# Sheet1.net
KiCad netlist of a schematic drawn in Altium Designer
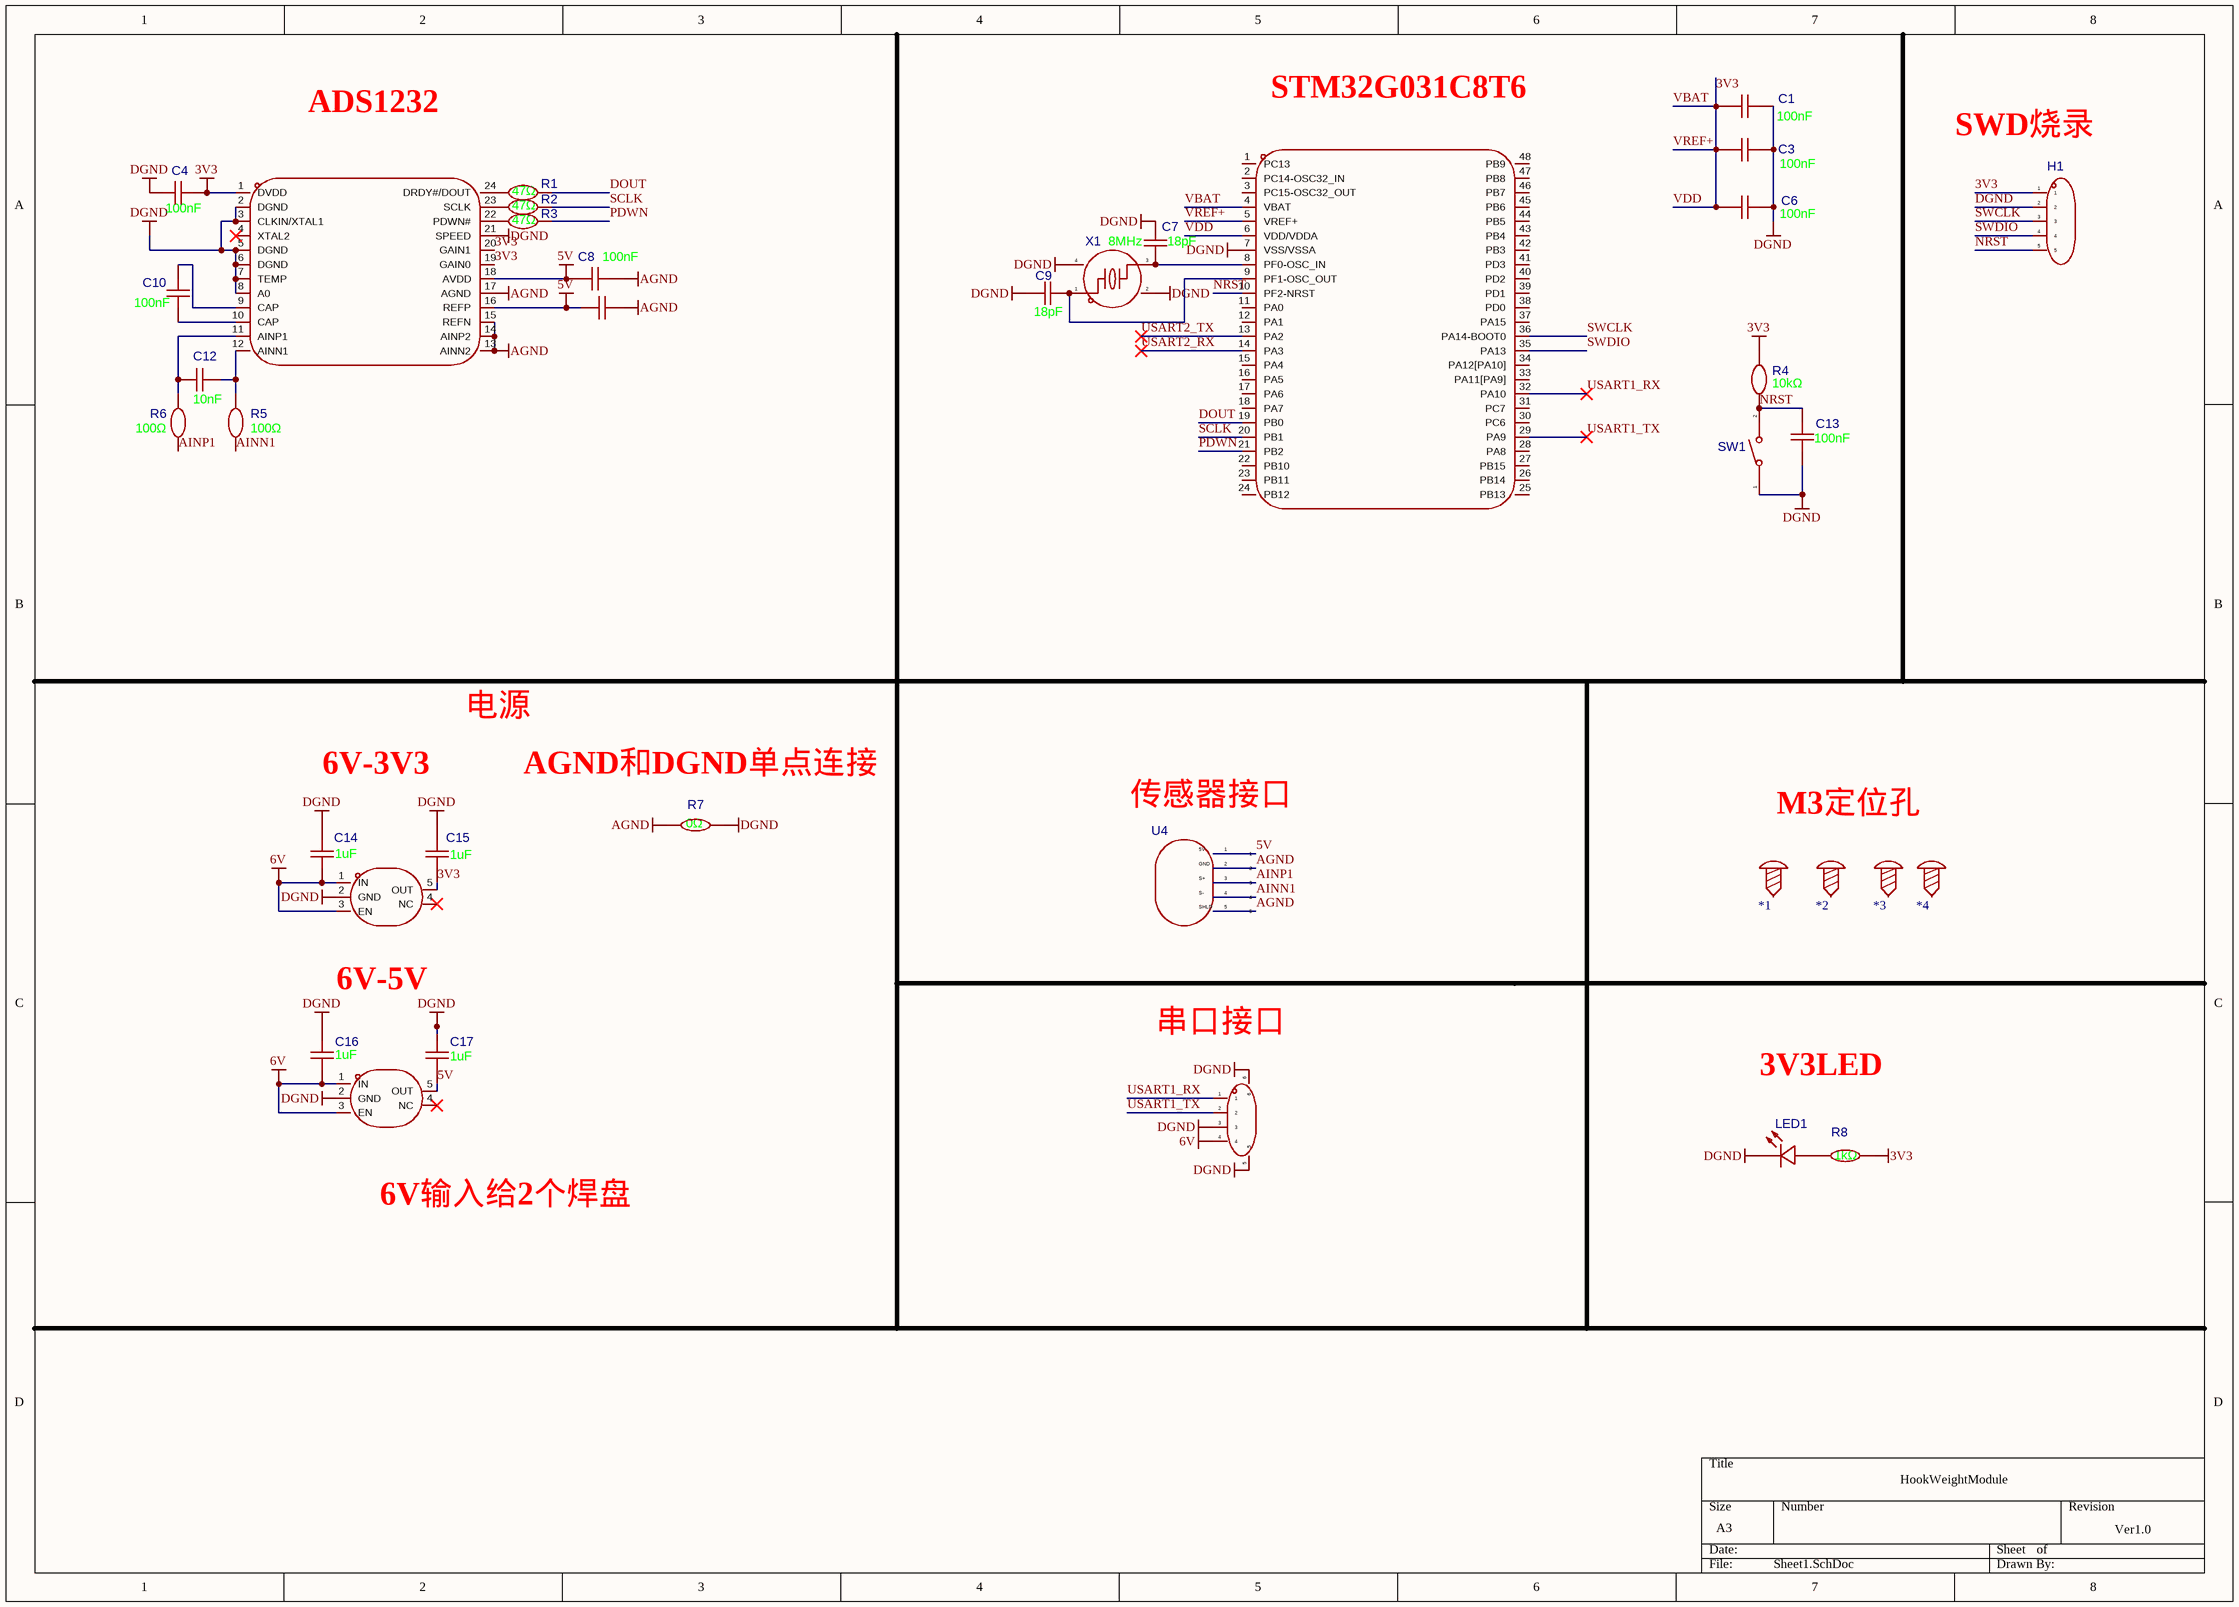
[diagram p0: Sheet1.SchDoc]

(export (version "E")
  (design (tool "Eeschema 10.0.6"))
  (components
    (comp (ref "*1") (value "螺丝孔_1") (footprint "M3螺丝") (libsource (lib "螺丝孔_1") (part "螺丝孔_1")))
    (comp (ref "*2") (value "螺丝孔_1") (footprint "M3螺丝") (libsource (lib "螺丝孔_1") (part "螺丝孔_1")))
    (comp (ref "*3") (value "螺丝孔_1") (footprint "M3螺丝") (libsource (lib "螺丝孔_1") (part "螺丝孔_1")))
    (comp (ref "*4") (value "螺丝孔_1") (footprint "M3螺丝") (libsource (lib "螺丝孔_1") (part "螺丝孔_1")))
    (comp (ref "C1")
      (value "100nF")
      (footprint "C0402")
      (description "容值:100nF;精度:±10%;额定电压:16V;温度系数:X7R;")
      (fields (field (name "MANUFACTURER") "YAGEO(国巨)") (field (name "MANUFACTURERPART") "CC0402KRX7R7BB104"))
      (libsource (lib "CC0402KRX7R7BB104") (part "cc0402krx7r7bb104"))
    )
    (comp (ref "C3")
      (value "100nF")
      (footprint "C0402")
      (description "容值:100nF;精度:±10%;额定电压:16V;温度系数:X7R;")
      (fields (field (name "MANUFACTURER") "YAGEO(国巨)") (field (name "MANUFACTURERPART") "CC0402KRX7R7BB104"))
      (libsource (lib "CC0402KRX7R7BB104") (part "cc0402krx7r7bb104"))
    )
    (comp (ref "C4")
      (value "100nF")
      (footprint "C0402")
      (description "容值:100nF;精度:±10%;额定电压:16V;温度系数:X7R;")
      (fields (field (name "MANUFACTURER") "YAGEO(国巨)") (field (name "MANUFACTURERPART") "CC0402KRX7R7BB104"))
      (libsource (lib "CC0402KRX7R7BB104") (part "cc0402krx7r7bb104"))
    )
    (comp (ref "C6")
      (value "100nF")
      (footprint "C0402")
      (description "容值:100nF;精度:±10%;额定电压:16V;温度系数:X7R;")
      (fields (field (name "MANUFACTURER") "YAGEO(国巨)") (field (name "MANUFACTURERPART") "CC0402KRX7R7BB104"))
      (libsource (lib "CC0402KRX7R7BB104") (part "cc0402krx7r7bb104"))
    )
    (comp (ref "C7")
      (value "18pF")
      (footprint "C0402")
      (description "容值:18pF;精度:±5%;额定电压:50V;温度系数:NP0;")
      (fields (field (name "MANUFACTURER") "YAGEO(国巨)") (field (name "MANUFACTURERPART") "CC0402JRNPO9BN180"))
      (libsource (lib "CC0402JRNPO9BN180") (part "cc0402jrnpo9bn180"))
    )
    (comp (ref "C8")
      (value "100nF")
      (footprint "C0402")
      (description "容值:100nF;精度:±10%;额定电压:16V;温度系数:X7R;")
      (fields (field (name "MANUFACTURER") "YAGEO(国巨)") (field (name "MANUFACTURERPART") "CC0402KRX7R7BB104"))
      (libsource (lib "CC0402KRX7R7BB104") (part "cc0402krx7r7bb104"))
    )
    (comp (ref "C9")
      (value "18pF")
      (footprint "C0402")
      (description "容值:18pF;精度:±5%;额定电压:50V;温度系数:NP0;")
      (fields (field (name "MANUFACTURER") "YAGEO(国巨)") (field (name "MANUFACTURERPART") "CC0402JRNPO9BN180"))
      (libsource (lib "CC0402JRNPO9BN180") (part "cc0402jrnpo9bn180"))
    )
    (comp (ref "C10")
      (value "100nF")
      (footprint "C0402")
      (description "容值:100nF;精度:±10%;额定电压:16V;温度系数:X7R;")
      (fields (field (name "MANUFACTURER") "YAGEO(国巨)") (field (name "MANUFACTURERPART") "CC0402KRX7R7BB104"))
      (libsource (lib "CC0402KRX7R7BB104") (part "cc0402krx7r7bb104"))
    )
    (comp (ref "C11")
      (value "cl21b103kbannnc")
      (footprint "C0805")
      (description "容值:10nF;精度:±10%;额定电压:50V;温度系数:X7R;")
      (fields (field (name "MANUFACTURER") "SAMSUNG(三星)") (field (name "MANUFACTURERPART") "CL21B103KBANNNC"))
      (libsource (lib "Schlib1") (part "cl21b103kbannnc"))
    )
    (comp (ref "C12")
      (value "10nF")
      (footprint "C0805")
      (description "容值:10nF;精度:±10%;额定电压:50V;温度系数:X7R;")
      (fields (field (name "MANUFACTURER") "SAMSUNG(三星)") (field (name "MANUFACTURERPART") "CL21B103KBANNNC"))
      (libsource (lib "Schlib1") (part "cl21b103kbannnc"))
    )
    (comp (ref "C13")
      (value "100nF")
      (footprint "C0402")
      (description "容值:100nF;精度:±10%;额定电压:16V;温度系数:X7R;")
      (fields (field (name "MANUFACTURER") "YAGEO(国巨)") (field (name "MANUFACTURERPART") "CC0402KRX7R7BB104"))
      (libsource (lib "CC0402KRX7R7BB104") (part "cc0402krx7r7bb104"))
    )
    (comp (ref "C14")
      (value "1uF")
      (footprint "C0603")
      (description "容值:1uF;精度:±10%;额定电压:50V;温度系数:X5R;")
      (fields (field (name "MANUFACTURER") "HRE(芯声)") (field (name "MANUFACTURERPART") "CGA0603X5R105K500JT"))
      (libsource (lib "CGA0603X5R105K500JT") (part "cga0603x5r105k500jt"))
    )
    (comp (ref "C15")
      (value "1uF")
      (footprint "C0603")
      (description "容值:1uF;精度:±10%;额定电压:50V;温度系数:X5R;")
      (fields (field (name "MANUFACTURER") "HRE(芯声)") (field (name "MANUFACTURERPART") "CGA0603X5R105K500JT"))
      (libsource (lib "CGA0603X5R105K500JT") (part "cga0603x5r105k500jt"))
    )
    (comp (ref "C16")
      (value "1uF")
      (footprint "C0603")
      (description "容值:1uF;精度:±10%;额定电压:50V;温度系数:X5R;")
      (fields (field (name "MANUFACTURER") "HRE(芯声)") (field (name "MANUFACTURERPART") "CGA0603X5R105K500JT"))
      (libsource (lib "CGA0603X5R105K500JT") (part "cga0603x5r105k500jt"))
    )
    (comp (ref "C17")
      (value "1uF")
      (footprint "C0603")
      (description "容值:1uF;精度:±10%;额定电压:50V;温度系数:X5R;")
      (fields (field (name "MANUFACTURER") "HRE(芯声)") (field (name "MANUFACTURERPART") "CGA0603X5R105K500JT"))
      (libsource (lib "CGA0603X5R105K500JT") (part "cga0603x5r105k500jt"))
    )
    (comp (ref "H1")
      (value "pz254v-11-05p")
      (footprint "HDR-TH_5P-P2.54-V-M")
      (fields (field (name "MANUFACTURER") "XFCN(兴飞)") (field (name "MANUFACTURERPART") "PZ254V-11-05P"))
      (libsource (lib "PZ254V-11-05P") (part "pz254v-11-05p"))
    )
    (comp (ref "LED1")
      (value "ltst-c190kskt")
      (footprint "LED0603-RD")
      (fields (field (name "MANUFACTURER") "LITEON(光宝)") (field (name "MANUFACTURERPART") "LTST-C190KSKT"))
      (libsource (lib "Schlib1") (part "ltst-c190kskt"))
    )
    (comp (ref "R1")
      (value "47Ω")
      (footprint "R0402")
      (description "电阻类型:厚膜电阻;阻值:47Ω;精度:±1%;功率:62.5mW;工作电压:50V;温度系数:±100ppm/℃;")
      (fields (field (name "MANUFACTURER") "FOJAN(富捷)") (field (name "MANUFACTURERPART") "FRC0402F47R0TS"))
      (libsource (lib "FRC0402F47R0TS") (part "frc0402f47r0ts"))
    )
    (comp (ref "R2")
      (value "47Ω")
      (footprint "R0402")
      (description "电阻类型:厚膜电阻;阻值:47Ω;精度:±1%;功率:62.5mW;工作电压:50V;温度系数:±100ppm/℃;")
      (fields (field (name "MANUFACTURER") "FOJAN(富捷)") (field (name "MANUFACTURERPART") "FRC0402F47R0TS"))
      (libsource (lib "FRC0402F47R0TS") (part "frc0402f47r0ts"))
    )
    (comp (ref "R3")
      (value "47Ω")
      (footprint "R0402")
      (description "电阻类型:厚膜电阻;阻值:47Ω;精度:±1%;功率:62.5mW;工作电压:50V;温度系数:±100ppm/℃;")
      (fields (field (name "MANUFACTURER") "FOJAN(富捷)") (field (name "MANUFACTURERPART") "FRC0402F47R0TS"))
      (libsource (lib "FRC0402F47R0TS") (part "frc0402f47r0ts"))
    )
    (comp (ref "R4")
      (value "10kΩ")
      (footprint "R0603")
      (description "电阻类型:厚膜电阻;阻值:10kΩ;精度:±1%;功率:100mW;工作电压:75V;温度系数:±100ppm/℃;")
      (fields (field (name "MANUFACTURER") "FOJAN(富捷)") (field (name "MANUFACTURERPART") "FRC0603F1002TS"))
      (libsource (lib "FRC0603F1002TS") (part "frc0603f1002ts"))
    )
    (comp (ref "R5")
      (value "100Ω")
      (footprint "R0603")
      (description "电阻类型:厚膜电阻;阻值:100Ω;精度:±1%;功率:100mW;工作电压:75V;温度系数:±100ppm/℃;")
      (fields (field (name "MANUFACTURER") "FOJAN(富捷)") (field (name "MANUFACTURERPART") "FRC0603F1000TS"))
      (libsource (lib "Schlib1") (part "frc0603f1000ts"))
    )
    (comp (ref "R6")
      (value "100Ω")
      (footprint "R0603")
      (description "电阻类型:厚膜电阻;阻值:100Ω;精度:±1%;功率:100mW;工作电压:75V;温度系数:±100ppm/℃;")
      (fields (field (name "MANUFACTURER") "FOJAN(富捷)") (field (name "MANUFACTURERPART") "FRC0603F1000TS"))
      (libsource (lib "Schlib1") (part "frc0603f1000ts"))
    )
    (comp (ref "R7")
      (value "0Ω")
      (footprint "R0603")
      (description "电阻类型:厚膜电阻;阻值:0Ω;精度:±1%;功率:100mW;工作电压:75V;温度系数:-;")
      (fields
        (field (name "MANUFACTURER") "UNI-ROYAL(厚声)")
        (field (name "MANUFACTURERPART") "0603WAF0000T5E")
      )
      (libsource (lib "0603WAF0000T5E") (part "0603waf0000t5e"))
    )
    (comp (ref "R8")
      (value "1kΩ")
      (footprint "R0603")
      (description "电阻类型:厚膜电阻;阻值:1kΩ;精度:±1%;功率:100mW;工作电压:75V;温度系数:±100ppm/℃;")
      (fields
        (field (name "MANUFACTURER") "UNI-ROYAL(厚声)")
        (field (name "MANUFACTURERPART") "0603WAF1001T5E")
      )
      (libsource (lib "Schlib1") (part "0603waf1001t5e"))
    )
    (comp (ref "SW1")
      (value "ts-1088-ar02016")
      (footprint "SW-SMD_L3.9-W3.0-P4.45")
      (fields (field (name "MANUFACTURER") "XUNPU(讯普)") (field (name "MANUFACTURERPART") "TS-1088-AR02016"))
      (libsource (lib "TS-1088-AR02016") (part "ts-1088-ar02016"))
    )
    (comp (ref "U2")
      (value "ads1232ipwr")
      (footprint "TSSOP-24_L7.8-W4.4-P0.65-LS6.4-BL")
      (description "分辨率(位):24;采样率:10Hz;工作电压:2.7V~5.3V;接口类型:SPI;")
      (fields (field (name "MANUFACTURER") "TI(德州仪器)") (field (name "MANUFACTURERPART") "ADS1232IPWR"))
      (libsource (lib "Schlib1") (part "ads1232ipwr"))
    )
    (comp (ref "U3")
      (value "stm32g031c8t6")
      (footprint "LQFP-48_L7.0-W7.0-P0.50-LS9.0-BL")
      (description "CPU内核:ARM Cortex-M0+;CPU最大主频:64MHz;CPU位数:32 Bit;")
      (fields (field (name "MANUFACTURER") "ST(意法半导体)") (field (name "MANUFACTURERPART") "STM32G031C8T6"))
      (libsource (lib "Schlib1") (part "stm32g031c8t6"))
    )
    (comp (ref "U4") (value "5个焊盘") (footprint "5个焊盘 - duplicate") (libsource (lib "5个焊盘") (part "5个焊盘")))
    (comp (ref "U5")
      (value "tps7a2033pdbvr")
      (footprint "SOT-23-5_L2.9-W1.6-P0.95-LS2.8-BR")
      (description "输出类型:固定;最大输入电压:6V;输出电压:3.3V;输出电流:300mA;输出极性:正极;")
      (fields (field (name "MANUFACTURER") "TI(德州仪器)") (field (name "MANUFACTURERPART") "TPS7A2033PDBVR"))
      (libsource (lib "Schlib1") (part "tps7a2033pdbvr"))
    )
    (comp (ref "U6")
      (value "tps7a2050pdbvr")
      (footprint "SOT-23-5_L2.9-W1.6-P0.95-LS2.8-BR")
      (description "输出极性:正极;工作电压:6V;输出电压:5V;输出电流:300mA;电源纹波抑制比(PSRR):65dB@(100Hz);输出类型:固定;")
      (fields (field (name "MANUFACTURER") "TI(德州仪器)") (field (name "MANUFACTURERPART") "TPS7A2050PDBVR"))
      (libsource (lib "Schlib1") (part "tps7a2050pdbvr"))
    )
    (comp (ref "U7")
      (value "bx-xh2.54-4pwt")
      (footprint "CONN-SMD_4P-P2.50_BX-XH2.54-4PWT")
      (fields (field (name "MANUFACTURER") "Bossie(博锡)") (field (name "MANUFACTURERPART") "BX-XH2.54-4PWT"))
      (libsource (lib "Schlib1") (part "bx-xh2.54-4pwt"))
    )
    (comp (ref "X1")
      (value "8MHz")
      (footprint "CRYSTAL-SMD_4P-L3.2-W2.5-BL")
      (description "晶振类型:贴片晶振;频率:8MHz;常温频差:±10ppm;负载电容:12pF;频率稳定度:±20ppm;")
      (fields (field (name "MANUFACTURER") "YXC(扬兴晶振)") (field (name "MANUFACTURERPART") "X32258MOB4SI"))
      (libsource (lib "X32258MOB4SI") (part "x32258mob4si"))
    )
  )
  (nets
    (net (code "1") (name "/AINN1") (class "Default")
      (node (ref "R5") (pin "1") (pinfunction "1_1") (pintype "passive"))
      (node (ref "U4") (pin "4") (pinfunction "4_4") (pintype "passive"))
    )
    (net (code "2") (name "/AINP1") (class "Default")
      (node (ref "R6") (pin "1") (pinfunction "1_1") (pintype "passive"))
      (node (ref "U4") (pin "3") (pinfunction "3_3") (pintype "passive"))
    )
    (net (code "3") (name "/DOUT") (class "Default")
      (node (ref "R1") (pin "2") (pinfunction "2_2") (pintype "passive"))
      (node (ref "U3") (pin "19") (pinfunction "PB0_19") (pintype "passive"))
    )
    (net (code "4") (name "/NRST") (class "Default")
      (node (ref "C13") (pin "2") (pinfunction "2_2") (pintype "passive"))
      (node (ref "H1") (pin "5") (pinfunction "5_5") (pintype "passive"))
      (node (ref "R4") (pin "1") (pinfunction "1_1") (pintype "passive"))
      (node (ref "SW1") (pin "2") (pinfunction "2_2") (pintype "passive"))
      (node (ref "U3") (pin "10") (pinfunction "PF2-NRST_10") (pintype "passive"))
    )
    (net (code "5") (name "/PDWN") (class "Default")
      (node (ref "R3") (pin "2") (pinfunction "2_2") (pintype "passive"))
      (node (ref "U3") (pin "21") (pinfunction "PB2_21") (pintype "passive"))
    )
    (net (code "6") (name "/SCLK") (class "Default")
      (node (ref "R2") (pin "2") (pinfunction "2_2") (pintype "passive"))
      (node (ref "U3") (pin "20") (pinfunction "PB1_20") (pintype "passive"))
    )
    (net (code "7") (name "/SWCLK") (class "Default")
      (node (ref "H1") (pin "3") (pinfunction "3_3") (pintype "passive"))
      (node (ref "U3") (pin "36") (pinfunction "PA14-BOOT0_36") (pintype "passive"))
    )
    (net (code "8") (name "/SWDIO") (class "Default")
      (node (ref "H1") (pin "4") (pinfunction "4_4") (pintype "passive"))
      (node (ref "U3") (pin "35") (pinfunction "PA13_35") (pintype "passive"))
    )
    (net (code "9") (name "/USART1_RX") (class "Default")
      (node (ref "U3") (pin "32") (pinfunction "PA10_32") (pintype "passive"))
      (node (ref "U7") (pin "1") (pinfunction "1_1") (pintype "passive"))
    )
    (net (code "10") (name "/USART1_TX") (class "Default")
      (node (ref "U3") (pin "29") (pinfunction "PA9_29") (pintype "passive"))
      (node (ref "U7") (pin "2") (pinfunction "2_2") (pintype "passive"))
    )
    (net (code "11") (name "/USART2_RX") (class "Default")
      (node (ref "U3") (pin "14") (pinfunction "PA3_14") (pintype "passive+no_connect"))
    )
    (net (code "12") (name "/USART2_TX") (class "Default")
      (node (ref "U3") (pin "13") (pinfunction "PA2_13") (pintype "passive+no_connect"))
    )
    (net (code "13") (name "3V3") (class "Default")
      (node (ref "C1") (pin "1") (pinfunction "1_1") (pintype "passive"))
      (node (ref "C15") (pin "1") (pinfunction "1_1") (pintype "passive"))
      (node (ref "C3") (pin "1") (pinfunction "1_1") (pintype "passive"))
      (node (ref "C4") (pin "2") (pinfunction "2_2") (pintype "passive"))
      (node (ref "C6") (pin "1") (pinfunction "1_1") (pintype "passive"))
      (node (ref "H1") (pin "1") (pinfunction "1_1") (pintype "passive"))
      (node (ref "R4") (pin "2") (pinfunction "2_2") (pintype "passive"))
      (node (ref "R8") (pin "2") (pinfunction "2_2") (pintype "passive"))
      (node (ref "U2") (pin "1") (pinfunction "DVDD_1") (pintype "passive"))
      (node (ref "U2") (pin "19") (pinfunction "GAIN0_19") (pintype "passive"))
      (node (ref "U2") (pin "20") (pinfunction "GAIN1_20") (pintype "passive"))
      (node (ref "U3") (pin "4") (pinfunction "VBAT_4") (pintype "passive"))
      (node (ref "U3") (pin "5") (pinfunction "VREF+_5") (pintype "passive"))
      (node (ref "U3") (pin "6") (pinfunction "VDD/VDDA_6") (pintype "passive"))
      (node (ref "U5") (pin "5") (pinfunction "OUT_5") (pintype "passive"))
    )
    (net (code "14") (name "5V") (class "Default")
      (node (ref "C11") (pin "1") (pinfunction "1_1") (pintype "passive"))
      (node (ref "C17") (pin "1") (pinfunction "1_1") (pintype "passive"))
      (node (ref "C8") (pin "1") (pinfunction "1_1") (pintype "passive"))
      (node (ref "U2") (pin "16") (pinfunction "REFP_16") (pintype "passive"))
      (node (ref "U2") (pin "18") (pinfunction "AVDD_18") (pintype "passive"))
      (node (ref "U4") (pin "1") (pinfunction "1_1") (pintype "passive"))
      (node (ref "U6") (pin "5") (pinfunction "OUT_5") (pintype "passive"))
    )
    (net (code "15") (name "6V") (class "Default")
      (node (ref "C14") (pin "1") (pinfunction "1_1") (pintype "passive"))
      (node (ref "C16") (pin "1") (pinfunction "1_1") (pintype "passive"))
      (node (ref "U5") (pin "1") (pinfunction "IN_1") (pintype "passive"))
      (node (ref "U5") (pin "3") (pinfunction "EN_3") (pintype "passive"))
      (node (ref "U6") (pin "1") (pinfunction "IN_1") (pintype "passive"))
      (node (ref "U6") (pin "3") (pinfunction "EN_3") (pintype "passive"))
      (node (ref "U7") (pin "4") (pinfunction "4_4") (pintype "passive"))
    )
    (net (code "16") (name "AGND") (class "Default")
      (node (ref "C11") (pin "2") (pinfunction "2_2") (pintype "passive"))
      (node (ref "C8") (pin "2") (pinfunction "2_2") (pintype "passive"))
      (node (ref "R7") (pin "1") (pinfunction "1_1") (pintype "passive"))
      (node (ref "U2") (pin "13") (pinfunction "AINN2_13") (pintype "passive"))
      (node (ref "U2") (pin "14") (pinfunction "AINP2_14") (pintype "passive"))
      (node (ref "U2") (pin "15") (pinfunction "REFN_15") (pintype "passive"))
      (node (ref "U2") (pin "17") (pinfunction "AGND_17") (pintype "passive"))
      (node (ref "U4") (pin "2") (pinfunction "2_2") (pintype "passive"))
      (node (ref "U4") (pin "5") (pinfunction "5_5") (pintype "passive"))
    )
    (net (code "17") (name "DGND") (class "Default")
      (node (ref "C1") (pin "2") (pinfunction "2_2") (pintype "passive"))
      (node (ref "C13") (pin "1") (pinfunction "1_1") (pintype "passive"))
      (node (ref "C14") (pin "2") (pinfunction "2_2") (pintype "passive"))
      (node (ref "C15") (pin "2") (pinfunction "2_2") (pintype "passive"))
      (node (ref "C16") (pin "2") (pinfunction "2_2") (pintype "passive"))
      (node (ref "C17") (pin "2") (pinfunction "2_2") (pintype "passive"))
      (node (ref "C3") (pin "2") (pinfunction "2_2") (pintype "passive"))
      (node (ref "C4") (pin "1") (pinfunction "1_1") (pintype "passive"))
      (node (ref "C6") (pin "2") (pinfunction "2_2") (pintype "passive"))
      (node (ref "C7") (pin "2") (pinfunction "2_2") (pintype "passive"))
      (node (ref "C9") (pin "1") (pinfunction "1_1") (pintype "passive"))
      (node (ref "H1") (pin "2") (pinfunction "2_2") (pintype "passive"))
      (node (ref "LED1") (pin "1") (pinfunction "-_1") (pintype "passive"))
      (node (ref "R7") (pin "2") (pinfunction "2_2") (pintype "passive"))
      (node (ref "SW1") (pin "1") (pinfunction "1_1") (pintype "passive"))
      (node (ref "U2") (pin "2") (pinfunction "DGND_2") (pintype "passive"))
      (node (ref "U2") (pin "21") (pinfunction "SPEED_21") (pintype "passive"))
      (node (ref "U2") (pin "3") (pinfunction "CLKIN/XTAL1_3") (pintype "passive"))
      (node (ref "U2") (pin "5") (pinfunction "DGND_5") (pintype "passive"))
      (node (ref "U2") (pin "6") (pinfunction "DGND_6") (pintype "passive"))
      (node (ref "U2") (pin "7") (pinfunction "TEMP_7") (pintype "passive"))
      (node (ref "U2") (pin "8") (pinfunction "A0_8") (pintype "passive"))
      (node (ref "U3") (pin "7") (pinfunction "VSS/VSSA_7") (pintype "passive"))
      (node (ref "U5") (pin "2") (pinfunction "GND_2") (pintype "passive"))
      (node (ref "U6") (pin "2") (pinfunction "GND_2") (pintype "passive"))
      (node (ref "U7") (pin "3") (pinfunction "3_3") (pintype "passive"))
      (node (ref "U7") (pin "5") (pinfunction "5_5") (pintype "passive"))
      (node (ref "U7") (pin "6") (pinfunction "6_6") (pintype "passive"))
      (node (ref "X1") (pin "2") (pinfunction "GND_2") (pintype "passive"))
      (node (ref "X1") (pin "4") (pinfunction "GND_4") (pintype "passive"))
    )
    (net (code "18") (name "Net-(C10-Pad1)") (class "Default")
      (node (ref "C10") (pin "1") (pinfunction "1_1") (pintype "passive"))
      (node (ref "U2") (pin "10") (pinfunction "CAP_10") (pintype "passive"))
    )
    (net (code "19") (name "Net-(C10-Pad2)") (class "Default")
      (node (ref "C10") (pin "2") (pinfunction "2_2") (pintype "passive"))
      (node (ref "U2") (pin "9") (pinfunction "CAP_9") (pintype "passive"))
    )
    (net (code "20") (name "Net-(LED1-+)") (class "Default")
      (node (ref "LED1") (pin "2") (pinfunction "+_2") (pintype "passive"))
      (node (ref "R8") (pin "1") (pinfunction "1_1") (pintype "passive"))
    )
    (net (code "21") (name "Net-(U2-AINN1)") (class "Default")
      (node (ref "C12") (pin "2") (pinfunction "2_2") (pintype "passive"))
      (node (ref "R5") (pin "2") (pinfunction "2_2") (pintype "passive"))
      (node (ref "U2") (pin "12") (pinfunction "AINN1_12") (pintype "passive"))
    )
    (net (code "22") (name "Net-(U2-AINP1)") (class "Default")
      (node (ref "C12") (pin "1") (pinfunction "1_1") (pintype "passive"))
      (node (ref "R6") (pin "2") (pinfunction "2_2") (pintype "passive"))
      (node (ref "U2") (pin "11") (pinfunction "AINP1_11") (pintype "passive"))
    )
    (net (code "23") (name "Net-(U2-DRDY#{slash}DOUT)") (class "Default")
      (node (ref "R1") (pin "1") (pinfunction "1_1") (pintype "passive"))
      (node (ref "U2") (pin "24") (pinfunction "DRDY#/DOUT_24") (pintype "passive"))
    )
    (net (code "24") (name "Net-(U2-PDWN#)") (class "Default")
      (node (ref "R3") (pin "1") (pinfunction "1_1") (pintype "passive"))
      (node (ref "U2") (pin "22") (pinfunction "PDWN#_22") (pintype "passive"))
    )
    (net (code "25") (name "Net-(U2-SCLK)") (class "Default")
      (node (ref "R2") (pin "1") (pinfunction "1_1") (pintype "passive"))
      (node (ref "U2") (pin "23") (pinfunction "SCLK_23") (pintype "passive"))
    )
    (net (code "26") (name "Net-(U3-PF0-OSC_IN)") (class "Default")
      (node (ref "C7") (pin "1") (pinfunction "1_1") (pintype "passive"))
      (node (ref "U3") (pin "8") (pinfunction "PF0-OSC_IN_8") (pintype "passive"))
      (node (ref "X1") (pin "3") (pinfunction "3_3") (pintype "passive"))
    )
    (net (code "27") (name "Net-(U3-PF1-OSC_OUT)") (class "Default")
      (node (ref "C9") (pin "2") (pinfunction "2_2") (pintype "passive"))
      (node (ref "U3") (pin "9") (pinfunction "PF1-OSC_OUT_9") (pintype "passive"))
      (node (ref "X1") (pin "1") (pinfunction "1_1") (pintype "passive"))
    )
    (net (code "28") (name "unconnected-(*1-Pad1)") (class "Default")
      (node (ref "*1") (pin "1") (pinfunction "1_1") (pintype "passive"))
    )
    (net (code "29") (name "unconnected-(*2-Pad1)") (class "Default")
      (node (ref "*2") (pin "1") (pinfunction "1_1") (pintype "passive"))
    )
    (net (code "30") (name "unconnected-(*3-Pad1)") (class "Default")
      (node (ref "*3") (pin "1") (pinfunction "1_1") (pintype "passive"))
    )
    (net (code "31") (name "unconnected-(*4-Pad1)") (class "Default")
      (node (ref "*4") (pin "1") (pinfunction "1_1") (pintype "passive"))
    )
    (net (code "32") (name "unconnected-(U2-XTAL2-Pad4)") (class "Default")
      (node (ref "U2") (pin "4") (pinfunction "XTAL2_4") (pintype "passive+no_connect"))
    )
    (net (code "33") (name "unconnected-(U3-PA0-Pad11)") (class "Default")
      (node (ref "U3") (pin "11") (pinfunction "PA0_11") (pintype "passive"))
    )
    (net (code "34") (name "unconnected-(U3-PA1-Pad12)") (class "Default")
      (node (ref "U3") (pin "12") (pinfunction "PA1_12") (pintype "passive"))
    )
    (net (code "35") (name "unconnected-(U3-PA4-Pad15)") (class "Default")
      (node (ref "U3") (pin "15") (pinfunction "PA4_15") (pintype "passive"))
    )
    (net (code "36") (name "unconnected-(U3-PA5-Pad16)") (class "Default")
      (node (ref "U3") (pin "16") (pinfunction "PA5_16") (pintype "passive"))
    )
    (net (code "37") (name "unconnected-(U3-PA6-Pad17)") (class "Default")
      (node (ref "U3") (pin "17") (pinfunction "PA6_17") (pintype "passive"))
    )
    (net (code "38") (name "unconnected-(U3-PA7-Pad18)") (class "Default")
      (node (ref "U3") (pin "18") (pinfunction "PA7_18") (pintype "passive"))
    )
    (net (code "39") (name "unconnected-(U3-PA8-Pad28)") (class "Default")
      (node (ref "U3") (pin "28") (pinfunction "PA8_28") (pintype "passive"))
    )
    (net (code "40") (name "unconnected-(U3-PA11[PA9]-Pad33)") (class "Default")
      (node (ref "U3") (pin "33") (pinfunction "PA11[PA9]_33") (pintype "passive"))
    )
    (net (code "41") (name "unconnected-(U3-PA12[PA10]-Pad34)") (class "Default")
      (node (ref "U3") (pin "34") (pinfunction "PA12[PA10]_34") (pintype "passive"))
    )
    (net (code "42") (name "unconnected-(U3-PA15-Pad37)") (class "Default")
      (node (ref "U3") (pin "37") (pinfunction "PA15_37") (pintype "passive"))
    )
    (net (code "43") (name "unconnected-(U3-PB3-Pad42)") (class "Default")
      (node (ref "U3") (pin "42") (pinfunction "PB3_42") (pintype "passive"))
    )
    (net (code "44") (name "unconnected-(U3-PB4-Pad43)") (class "Default")
      (node (ref "U3") (pin "43") (pinfunction "PB4_43") (pintype "passive"))
    )
    (net (code "45") (name "unconnected-(U3-PB5-Pad44)") (class "Default")
      (node (ref "U3") (pin "44") (pinfunction "PB5_44") (pintype "passive"))
    )
    (net (code "46") (name "unconnected-(U3-PB6-Pad45)") (class "Default")
      (node (ref "U3") (pin "45") (pinfunction "PB6_45") (pintype "passive"))
    )
    (net (code "47") (name "unconnected-(U3-PB7-Pad46)") (class "Default")
      (node (ref "U3") (pin "46") (pinfunction "PB7_46") (pintype "passive"))
    )
    (net (code "48") (name "unconnected-(U3-PB8-Pad47)") (class "Default")
      (node (ref "U3") (pin "47") (pinfunction "PB8_47") (pintype "passive"))
    )
    (net (code "49") (name "unconnected-(U3-PB9-Pad48)") (class "Default")
      (node (ref "U3") (pin "48") (pinfunction "PB9_48") (pintype "passive"))
    )
    (net (code "50") (name "unconnected-(U3-PB10-Pad22)") (class "Default")
      (node (ref "U3") (pin "22") (pinfunction "PB10_22") (pintype "passive"))
    )
    (net (code "51") (name "unconnected-(U3-PB11-Pad23)") (class "Default")
      (node (ref "U3") (pin "23") (pinfunction "PB11_23") (pintype "passive"))
    )
    (net (code "52") (name "unconnected-(U3-PB12-Pad24)") (class "Default")
      (node (ref "U3") (pin "24") (pinfunction "PB12_24") (pintype "passive"))
    )
    (net (code "53") (name "unconnected-(U3-PB13-Pad25)") (class "Default")
      (node (ref "U3") (pin "25") (pinfunction "PB13_25") (pintype "passive"))
    )
    (net (code "54") (name "unconnected-(U3-PB14-Pad26)") (class "Default")
      (node (ref "U3") (pin "26") (pinfunction "PB14_26") (pintype "passive"))
    )
    (net (code "55") (name "unconnected-(U3-PB15-Pad27)") (class "Default")
      (node (ref "U3") (pin "27") (pinfunction "PB15_27") (pintype "passive"))
    )
    (net (code "56") (name "unconnected-(U3-PC6-Pad30)") (class "Default")
      (node (ref "U3") (pin "30") (pinfunction "PC6_30") (pintype "passive"))
    )
    (net (code "57") (name "unconnected-(U3-PC7-Pad31)") (class "Default")
      (node (ref "U3") (pin "31") (pinfunction "PC7_31") (pintype "passive"))
    )
    (net (code "58") (name "unconnected-(U3-PC13-Pad1)") (class "Default")
      (node (ref "U3") (pin "1") (pinfunction "PC13_1") (pintype "passive"))
    )
    (net (code "59") (name "unconnected-(U3-PC14-OSC32_IN-Pad2)") (class "Default")
      (node (ref "U3") (pin "2") (pinfunction "PC14-OSC32_IN_2") (pintype "passive"))
    )
    (net (code "60") (name "unconnected-(U3-PC15-OSC32_OUT-Pad3)") (class "Default")
      (node (ref "U3") (pin "3") (pinfunction "PC15-OSC32_OUT_3") (pintype "passive"))
    )
    (net (code "61") (name "unconnected-(U3-PD0-Pad38)") (class "Default")
      (node (ref "U3") (pin "38") (pinfunction "PD0_38") (pintype "passive"))
    )
    (net (code "62") (name "unconnected-(U3-PD1-Pad39)") (class "Default")
      (node (ref "U3") (pin "39") (pinfunction "PD1_39") (pintype "passive"))
    )
    (net (code "63") (name "unconnected-(U3-PD2-Pad40)") (class "Default")
      (node (ref "U3") (pin "40") (pinfunction "PD2_40") (pintype "passive"))
    )
    (net (code "64") (name "unconnected-(U3-PD3-Pad41)") (class "Default")
      (node (ref "U3") (pin "41") (pinfunction "PD3_41") (pintype "passive"))
    )
    (net (code "65") (name "unconnected-(U5-NC-Pad4)") (class "Default")
      (node (ref "U5") (pin "4") (pinfunction "NC_4") (pintype "passive+no_connect"))
    )
    (net (code "66") (name "unconnected-(U6-NC-Pad4)") (class "Default")
      (node (ref "U6") (pin "4") (pinfunction "NC_4") (pintype "passive+no_connect"))
    )
  )
)
